# airball_sensor_board_v3.net
KiCad netlist of a schematic drawn in EAGLE
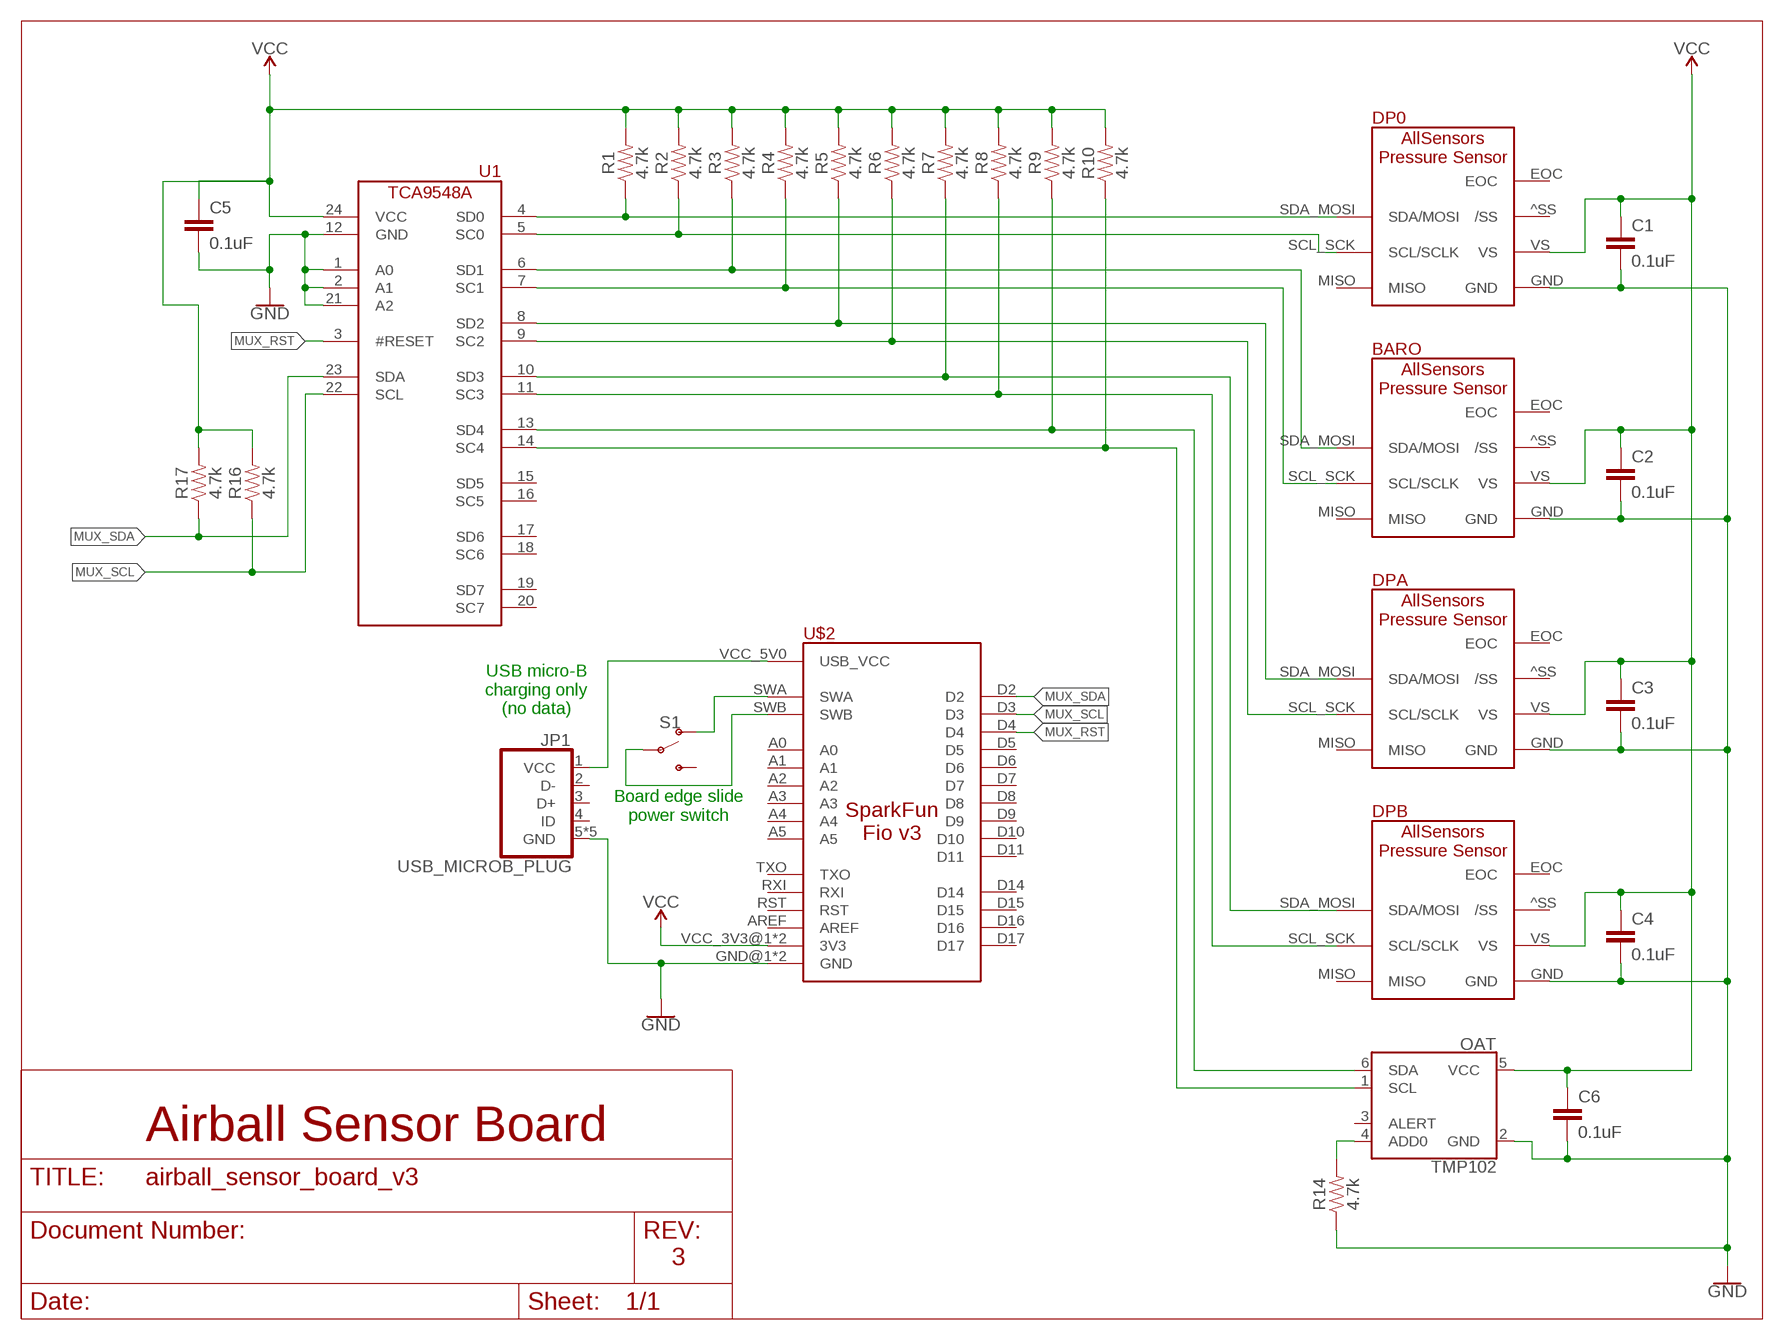
[diagram p0: schematic, sheet 1]

(export (version "E")
  (design (tool "Eeschema 10.0.6"))
  (components
    (comp (ref "BARO")
      (value "ALL_SENSORS_DLHR_E1ND")
      (footprint "eagle-import:ALL_SENSORS_E1BD_8PIN_THRU")
      (libsource (lib "eagle-import") (part "ALL_SENSORS_DLHR_E1ND"))
    )
    (comp (ref "C1")
      (value "0.1uF")
      (footprint "eagle-import:0603")
      (libsource (lib "eagle-import") (part "0.1UF-0603-25V-5%"))
    )
    (comp (ref "C2")
      (value "0.1uF")
      (footprint "eagle-import:0603")
      (libsource (lib "eagle-import") (part "0.1UF-0603-25V-5%"))
    )
    (comp (ref "C3")
      (value "0.1uF")
      (footprint "eagle-import:0603")
      (libsource (lib "eagle-import") (part "0.1UF-0603-25V-5%"))
    )
    (comp (ref "C4")
      (value "0.1uF")
      (footprint "eagle-import:0603")
      (libsource (lib "eagle-import") (part "0.1UF-0603-25V-5%"))
    )
    (comp (ref "C5")
      (value "0.1uF")
      (footprint "eagle-import:0603")
      (libsource (lib "eagle-import") (part "0.1UF-0603-25V-5%"))
    )
    (comp (ref "C6")
      (value "0.1uF")
      (footprint "eagle-import:0603")
      (libsource (lib "eagle-import") (part "0.1UF-0603-25V-5%"))
    )
    (comp (ref "DP0")
      (value "ALL_SENSORS_DLHR_E1ND")
      (footprint "eagle-import:ALL_SENSORS_E1BD_8PIN_THRU")
      (libsource (lib "eagle-import") (part "ALL_SENSORS_DLHR_E1ND"))
    )
    (comp (ref "DPA")
      (value "ALL_SENSORS_DLHR_E1ND")
      (footprint "eagle-import:ALL_SENSORS_E1BD_8PIN_THRU")
      (libsource (lib "eagle-import") (part "ALL_SENSORS_DLHR_E1ND"))
    )
    (comp (ref "DPB")
      (value "ALL_SENSORS_DLHR_E1ND")
      (footprint "eagle-import:ALL_SENSORS_E1BD_8PIN_THRU")
      (libsource (lib "eagle-import") (part "ALL_SENSORS_DLHR_E1ND"))
    )
    (comp (ref "JP1")
      (value "USB_MICROB_PLUG")
      (footprint "eagle-import:USB_MICRO_B_TYCO")
      (libsource (lib "eagle-import") (part "USB_MICROB_PLUG"))
    )
    (comp (ref "OAT")
      (value "TMP102")
      (footprint "eagle-import:SOT563")
      (libsource (lib "eagle-import") (part "TMP102"))
    )
    (comp (ref "R1")
      (value "4.7k")
      (footprint "eagle-import:0603")
      (libsource (lib "eagle-import") (part "4.7KOHM-0603-1/10W-1%"))
    )
    (comp (ref "R2")
      (value "4.7k")
      (footprint "eagle-import:0603")
      (libsource (lib "eagle-import") (part "4.7KOHM-0603-1/10W-1%"))
    )
    (comp (ref "R3")
      (value "4.7k")
      (footprint "eagle-import:0603")
      (libsource (lib "eagle-import") (part "4.7KOHM-0603-1/10W-1%"))
    )
    (comp (ref "R4")
      (value "4.7k")
      (footprint "eagle-import:0603")
      (libsource (lib "eagle-import") (part "4.7KOHM-0603-1/10W-1%"))
    )
    (comp (ref "R5")
      (value "4.7k")
      (footprint "eagle-import:0603")
      (libsource (lib "eagle-import") (part "4.7KOHM-0603-1/10W-1%"))
    )
    (comp (ref "R6")
      (value "4.7k")
      (footprint "eagle-import:0603")
      (libsource (lib "eagle-import") (part "4.7KOHM-0603-1/10W-1%"))
    )
    (comp (ref "R7")
      (value "4.7k")
      (footprint "eagle-import:0603")
      (libsource (lib "eagle-import") (part "4.7KOHM-0603-1/10W-1%"))
    )
    (comp (ref "R8")
      (value "4.7k")
      (footprint "eagle-import:0603")
      (libsource (lib "eagle-import") (part "4.7KOHM-0603-1/10W-1%"))
    )
    (comp (ref "R9")
      (value "4.7k")
      (footprint "eagle-import:0603")
      (libsource (lib "eagle-import") (part "4.7KOHM-0603-1/10W-1%"))
    )
    (comp (ref "R10")
      (value "4.7k")
      (footprint "eagle-import:0603")
      (libsource (lib "eagle-import") (part "4.7KOHM-0603-1/10W-1%"))
    )
    (comp (ref "R14")
      (value "4.7k")
      (footprint "eagle-import:0603")
      (libsource (lib "eagle-import") (part "4.7KOHM-0603-1/10W-1%"))
    )
    (comp (ref "R16")
      (value "4.7k")
      (footprint "eagle-import:0603")
      (libsource (lib "eagle-import") (part "4.7KOHM-0603-1/10W-1%"))
    )
    (comp (ref "R17")
      (value "4.7k")
      (footprint "eagle-import:0603")
      (libsource (lib "eagle-import") (part "4.7KOHM-0603-1/10W-1%"))
    )
    (comp (ref "S1")
      (value "SWITCH-SPDT-SMD-RIGHT-ANGLE")
      (footprint "eagle-import:SWITCH_SPST_SMD_A")
      (libsource (lib "eagle-import") (part "SWITCH-SPDT-SMD-RIGHT-ANGLE"))
    )
    (comp (ref "U$2")
      (value "SPARKFUN_FIO_V3")
      (footprint "eagle-import:SPARKFUN_FIO_V3")
      (libsource (lib "eagle-import") (part "SPARKFUN_FIO_V3"))
    )
    (comp (ref "U1")
      (value "TCA9548ATSSOP24")
      (footprint "eagle-import:TSSOP24")
      (libsource (lib "eagle-import") (part "TCA9548ATSSOP24"))
    )
  )
  (nets
    (net (code "1") (name "GND") (class "Default")
      (node (ref "BARO") (pin "GND") (pinfunction "GND_GND") (pintype "power_in"))
      (node (ref "C1") (pin "2") (pinfunction "2_2") (pintype "passive"))
      (node (ref "C2") (pin "2") (pinfunction "2_2") (pintype "passive"))
      (node (ref "C3") (pin "2") (pinfunction "2_2") (pintype "passive"))
      (node (ref "C4") (pin "2") (pinfunction "2_2") (pintype "passive"))
      (node (ref "C5") (pin "2") (pinfunction "2_2") (pintype "passive"))
      (node (ref "C6") (pin "2") (pinfunction "2_2") (pintype "passive"))
      (node (ref "DP0") (pin "GND") (pinfunction "GND_GND") (pintype "power_in"))
      (node (ref "DPA") (pin "GND") (pinfunction "GND_GND") (pintype "power_in"))
      (node (ref "DPB") (pin "GND") (pinfunction "GND_GND") (pintype "power_in"))
      (node (ref "JP1") (pin "5") (pinfunction "GND_5") (pintype "bidirectional"))
      (node (ref "JP1") (pin "SH@1") (pinfunction "GND_SH@1") (pintype "bidirectional"))
      (node (ref "JP1") (pin "SH@2") (pinfunction "GND_SH@2") (pintype "bidirectional"))
      (node (ref "JP1") (pin "SH@3") (pinfunction "GND_SH@3") (pintype "bidirectional"))
      (node (ref "JP1") (pin "SH@4") (pinfunction "GND_SH@4") (pintype "bidirectional"))
      (node (ref "OAT") (pin "2") (pinfunction "GND_2") (pintype "bidirectional"))
      (node (ref "R14") (pin "1") (pinfunction "1_1") (pintype "passive"))
      (node (ref "U$2") (pin "GND@1") (pinfunction "GND_GND@1") (pintype "power_in"))
      (node (ref "U$2") (pin "GND@2") (pinfunction "GND_GND@2") (pintype "power_in"))
      (node (ref "U1") (pin "1") (pinfunction "A0_1") (pintype "bidirectional"))
      (node (ref "U1") (pin "12") (pinfunction "GND_12") (pintype "bidirectional"))
      (node (ref "U1") (pin "2") (pinfunction "A1_2") (pintype "bidirectional"))
      (node (ref "U1") (pin "21") (pinfunction "A2_21") (pintype "bidirectional"))
    )
    (net (code "2") (name "MUX_RST") (class "Default")
      (node (ref "U$2") (pin "D4") (pinfunction "D4_D4") (pintype "bidirectional"))
      (node (ref "U1") (pin "3") (pinfunction "#RESET_3") (pintype "bidirectional"))
    )
    (net (code "3") (name "MUX_SCL") (class "Default")
      (node (ref "R16") (pin "1") (pinfunction "1_1") (pintype "passive"))
      (node (ref "U$2") (pin "D3") (pinfunction "D3_D3") (pintype "bidirectional"))
      (node (ref "U1") (pin "22") (pinfunction "SCL_22") (pintype "bidirectional"))
    )
    (net (code "4") (name "MUX_SDA") (class "Default")
      (node (ref "R17") (pin "1") (pinfunction "1_1") (pintype "passive"))
      (node (ref "U$2") (pin "D2") (pinfunction "D2_D2") (pintype "bidirectional"))
      (node (ref "U1") (pin "23") (pinfunction "SDA_23") (pintype "bidirectional"))
    )
    (net (code "5") (name "Net-(BARO-SCL{slash}SCLK)") (class "Default")
      (node (ref "BARO") (pin "SCL_SCK") (pinfunction "SCL/SCLK_SCL_SCK") (pintype "bidirectional"))
      (node (ref "R4") (pin "1") (pinfunction "1_1") (pintype "passive"))
      (node (ref "U1") (pin "7") (pinfunction "SC1_7") (pintype "bidirectional"))
    )
    (net (code "6") (name "Net-(BARO-SDA{slash}MOSI)") (class "Default")
      (node (ref "BARO") (pin "SDA_MOSI") (pinfunction "SDA/MOSI_SDA_MOSI") (pintype "bidirectional"))
      (node (ref "R3") (pin "1") (pinfunction "1_1") (pintype "passive"))
      (node (ref "U1") (pin "6") (pinfunction "SD1_6") (pintype "bidirectional"))
    )
    (net (code "7") (name "Net-(DP0-SCL{slash}SCLK)") (class "Default")
      (node (ref "DP0") (pin "SCL_SCK") (pinfunction "SCL/SCLK_SCL_SCK") (pintype "bidirectional"))
      (node (ref "R2") (pin "1") (pinfunction "1_1") (pintype "passive"))
      (node (ref "U1") (pin "5") (pinfunction "SC0_5") (pintype "bidirectional"))
    )
    (net (code "8") (name "Net-(DP0-SDA{slash}MOSI)") (class "Default")
      (node (ref "DP0") (pin "SDA_MOSI") (pinfunction "SDA/MOSI_SDA_MOSI") (pintype "bidirectional"))
      (node (ref "R1") (pin "1") (pinfunction "1_1") (pintype "passive"))
      (node (ref "U1") (pin "4") (pinfunction "SD0_4") (pintype "bidirectional"))
    )
    (net (code "9") (name "Net-(DPA-SCL{slash}SCLK)") (class "Default")
      (node (ref "DPA") (pin "SCL_SCK") (pinfunction "SCL/SCLK_SCL_SCK") (pintype "bidirectional"))
      (node (ref "R6") (pin "1") (pinfunction "1_1") (pintype "passive"))
      (node (ref "U1") (pin "9") (pinfunction "SC2_9") (pintype "bidirectional"))
    )
    (net (code "10") (name "Net-(DPA-SDA{slash}MOSI)") (class "Default")
      (node (ref "DPA") (pin "SDA_MOSI") (pinfunction "SDA/MOSI_SDA_MOSI") (pintype "bidirectional"))
      (node (ref "R5") (pin "1") (pinfunction "1_1") (pintype "passive"))
      (node (ref "U1") (pin "8") (pinfunction "SD2_8") (pintype "bidirectional"))
    )
    (net (code "11") (name "Net-(DPB-SCL{slash}SCLK)") (class "Default")
      (node (ref "DPB") (pin "SCL_SCK") (pinfunction "SCL/SCLK_SCL_SCK") (pintype "bidirectional"))
      (node (ref "R8") (pin "1") (pinfunction "1_1") (pintype "passive"))
      (node (ref "U1") (pin "11") (pinfunction "SC3_11") (pintype "bidirectional"))
    )
    (net (code "12") (name "Net-(DPB-SDA{slash}MOSI)") (class "Default")
      (node (ref "DPB") (pin "SDA_MOSI") (pinfunction "SDA/MOSI_SDA_MOSI") (pintype "bidirectional"))
      (node (ref "R7") (pin "1") (pinfunction "1_1") (pintype "passive"))
      (node (ref "U1") (pin "10") (pinfunction "SD3_10") (pintype "bidirectional"))
    )
    (net (code "13") (name "Net-(JP1-VCC)") (class "Default")
      (node (ref "JP1") (pin "1") (pinfunction "VCC_1") (pintype "bidirectional"))
      (node (ref "U$2") (pin "VCC_5V0") (pinfunction "USB_VCC_VCC_5V0") (pintype "power_in"))
    )
    (net (code "14") (name "Net-(OAT-ADD0)") (class "Default")
      (node (ref "OAT") (pin "4") (pinfunction "ADD0_4") (pintype "bidirectional"))
      (node (ref "R14") (pin "2") (pinfunction "2_2") (pintype "passive"))
    )
    (net (code "15") (name "Net-(OAT-SCL)") (class "Default")
      (node (ref "OAT") (pin "1") (pinfunction "SCL_1") (pintype "bidirectional"))
      (node (ref "R10") (pin "1") (pinfunction "1_1") (pintype "passive"))
      (node (ref "U1") (pin "14") (pinfunction "SC4_14") (pintype "bidirectional"))
    )
    (net (code "16") (name "Net-(OAT-SDA)") (class "Default")
      (node (ref "OAT") (pin "6") (pinfunction "SDA_6") (pintype "bidirectional"))
      (node (ref "R9") (pin "1") (pinfunction "1_1") (pintype "passive"))
      (node (ref "U1") (pin "13") (pinfunction "SD4_13") (pintype "bidirectional"))
    )
    (net (code "17") (name "Net-(S1-O)") (class "Default")
      (node (ref "S1") (pin "1") (pinfunction "O_1") (pintype "passive"))
      (node (ref "U$2") (pin "SWA") (pinfunction "SWA_SWA") (pintype "bidirectional"))
    )
    (net (code "18") (name "Net-(S1-P)") (class "Default")
      (node (ref "S1") (pin "2") (pinfunction "P_2") (pintype "passive"))
      (node (ref "U$2") (pin "SWB") (pinfunction "SWB_SWB") (pintype "bidirectional"))
    )
    (net (code "19") (name "VCC") (class "Default")
      (node (ref "BARO") (pin "VS") (pinfunction "VS_VS") (pintype "power_in"))
      (node (ref "C1") (pin "1") (pinfunction "1_1") (pintype "passive"))
      (node (ref "C2") (pin "1") (pinfunction "1_1") (pintype "passive"))
      (node (ref "C3") (pin "1") (pinfunction "1_1") (pintype "passive"))
      (node (ref "C4") (pin "1") (pinfunction "1_1") (pintype "passive"))
      (node (ref "C5") (pin "1") (pinfunction "1_1") (pintype "passive"))
      (node (ref "C6") (pin "1") (pinfunction "1_1") (pintype "passive"))
      (node (ref "DP0") (pin "VS") (pinfunction "VS_VS") (pintype "power_in"))
      (node (ref "DPA") (pin "VS") (pinfunction "VS_VS") (pintype "power_in"))
      (node (ref "DPB") (pin "VS") (pinfunction "VS_VS") (pintype "power_in"))
      (node (ref "OAT") (pin "5") (pinfunction "VCC_5") (pintype "bidirectional"))
      (node (ref "R1") (pin "2") (pinfunction "2_2") (pintype "passive"))
      (node (ref "R10") (pin "2") (pinfunction "2_2") (pintype "passive"))
      (node (ref "R16") (pin "2") (pinfunction "2_2") (pintype "passive"))
      (node (ref "R17") (pin "2") (pinfunction "2_2") (pintype "passive"))
      (node (ref "R2") (pin "2") (pinfunction "2_2") (pintype "passive"))
      (node (ref "R3") (pin "2") (pinfunction "2_2") (pintype "passive"))
      (node (ref "R4") (pin "2") (pinfunction "2_2") (pintype "passive"))
      (node (ref "R5") (pin "2") (pinfunction "2_2") (pintype "passive"))
      (node (ref "R6") (pin "2") (pinfunction "2_2") (pintype "passive"))
      (node (ref "R7") (pin "2") (pinfunction "2_2") (pintype "passive"))
      (node (ref "R8") (pin "2") (pinfunction "2_2") (pintype "passive"))
      (node (ref "R9") (pin "2") (pinfunction "2_2") (pintype "passive"))
      (node (ref "U$2") (pin "VCC_3V3@1") (pinfunction "3V3_VCC_3V3@1") (pintype "power_in"))
      (node (ref "U$2") (pin "VCC_3V3@2") (pinfunction "3V3_VCC_3V3@2") (pintype "power_in"))
      (node (ref "U1") (pin "24") (pinfunction "VCC_24") (pintype "bidirectional"))
    )
    (net (code "20") (name "unconnected-(BARO-PadEOC)") (class "Default")
      (node (ref "BARO") (pin "EOC") (pinfunction "EOC_EOC") (pintype "bidirectional"))
    )
    (net (code "21") (name "unconnected-(BARO-PadMISO)") (class "Default")
      (node (ref "BARO") (pin "MISO") (pinfunction "MISO_MISO") (pintype "input"))
    )
    (net (code "22") (name "unconnected-(BARO-{slash}SS-Pad^SS)") (class "Default")
      (node (ref "BARO") (pin "^SS") (pinfunction "/SS_^SS") (pintype "input"))
    )
    (net (code "23") (name "unconnected-(DP0-PadEOC)") (class "Default")
      (node (ref "DP0") (pin "EOC") (pinfunction "EOC_EOC") (pintype "bidirectional"))
    )
    (net (code "24") (name "unconnected-(DP0-PadMISO)") (class "Default")
      (node (ref "DP0") (pin "MISO") (pinfunction "MISO_MISO") (pintype "input"))
    )
    (net (code "25") (name "unconnected-(DP0-{slash}SS-Pad^SS)") (class "Default")
      (node (ref "DP0") (pin "^SS") (pinfunction "/SS_^SS") (pintype "input"))
    )
    (net (code "26") (name "unconnected-(DPA-PadEOC)") (class "Default")
      (node (ref "DPA") (pin "EOC") (pinfunction "EOC_EOC") (pintype "bidirectional"))
    )
    (net (code "27") (name "unconnected-(DPA-PadMISO)") (class "Default")
      (node (ref "DPA") (pin "MISO") (pinfunction "MISO_MISO") (pintype "input"))
    )
    (net (code "28") (name "unconnected-(DPA-{slash}SS-Pad^SS)") (class "Default")
      (node (ref "DPA") (pin "^SS") (pinfunction "/SS_^SS") (pintype "input"))
    )
    (net (code "29") (name "unconnected-(DPB-PadEOC)") (class "Default")
      (node (ref "DPB") (pin "EOC") (pinfunction "EOC_EOC") (pintype "bidirectional"))
    )
    (net (code "30") (name "unconnected-(DPB-PadMISO)") (class "Default")
      (node (ref "DPB") (pin "MISO") (pinfunction "MISO_MISO") (pintype "input"))
    )
    (net (code "31") (name "unconnected-(DPB-{slash}SS-Pad^SS)") (class "Default")
      (node (ref "DPB") (pin "^SS") (pinfunction "/SS_^SS") (pintype "input"))
    )
    (net (code "32") (name "unconnected-(JP1-D+-Pad3)") (class "Default")
      (node (ref "JP1") (pin "3") (pinfunction "D+_3") (pintype "bidirectional"))
    )
    (net (code "33") (name "unconnected-(JP1-D--Pad2)") (class "Default")
      (node (ref "JP1") (pin "2") (pinfunction "D-_2") (pintype "bidirectional"))
    )
    (net (code "34") (name "unconnected-(JP1-ID-Pad4)") (class "Default")
      (node (ref "JP1") (pin "4") (pinfunction "ID_4") (pintype "bidirectional"))
    )
    (net (code "35") (name "unconnected-(OAT-ALERT-Pad3)") (class "Default")
      (node (ref "OAT") (pin "3") (pinfunction "ALERT_3") (pintype "bidirectional"))
    )
    (net (code "36") (name "unconnected-(S1-S-Pad3)") (class "Default")
      (node (ref "S1") (pin "3") (pinfunction "S_3") (pintype "passive"))
    )
    (net (code "37") (name "unconnected-(U$2-PadA0)") (class "Default")
      (node (ref "U$2") (pin "A0") (pinfunction "A0_A0") (pintype "bidirectional"))
    )
    (net (code "38") (name "unconnected-(U$2-PadA1)") (class "Default")
      (node (ref "U$2") (pin "A1") (pinfunction "A1_A1") (pintype "bidirectional"))
    )
    (net (code "39") (name "unconnected-(U$2-PadA2)") (class "Default")
      (node (ref "U$2") (pin "A2") (pinfunction "A2_A2") (pintype "bidirectional"))
    )
    (net (code "40") (name "unconnected-(U$2-PadA3)") (class "Default")
      (node (ref "U$2") (pin "A3") (pinfunction "A3_A3") (pintype "bidirectional"))
    )
    (net (code "41") (name "unconnected-(U$2-PadA4)") (class "Default")
      (node (ref "U$2") (pin "A4") (pinfunction "A4_A4") (pintype "bidirectional"))
    )
    (net (code "42") (name "unconnected-(U$2-PadA5)") (class "Default")
      (node (ref "U$2") (pin "A5") (pinfunction "A5_A5") (pintype "bidirectional"))
    )
    (net (code "43") (name "unconnected-(U$2-PadAREF)") (class "Default")
      (node (ref "U$2") (pin "AREF") (pinfunction "AREF_AREF") (pintype "bidirectional"))
    )
    (net (code "44") (name "unconnected-(U$2-PadD5)") (class "Default")
      (node (ref "U$2") (pin "D5") (pinfunction "D5_D5") (pintype "bidirectional"))
    )
    (net (code "45") (name "unconnected-(U$2-PadD6)") (class "Default")
      (node (ref "U$2") (pin "D6") (pinfunction "D6_D6") (pintype "bidirectional"))
    )
    (net (code "46") (name "unconnected-(U$2-PadD7)") (class "Default")
      (node (ref "U$2") (pin "D7") (pinfunction "D7_D7") (pintype "bidirectional"))
    )
    (net (code "47") (name "unconnected-(U$2-PadD8)") (class "Default")
      (node (ref "U$2") (pin "D8") (pinfunction "D8_D8") (pintype "bidirectional"))
    )
    (net (code "48") (name "unconnected-(U$2-PadD9)") (class "Default")
      (node (ref "U$2") (pin "D9") (pinfunction "D9_D9") (pintype "bidirectional"))
    )
    (net (code "49") (name "unconnected-(U$2-PadD10)") (class "Default")
      (node (ref "U$2") (pin "D10") (pinfunction "D10_D10") (pintype "bidirectional"))
    )
    (net (code "50") (name "unconnected-(U$2-PadD11)") (class "Default")
      (node (ref "U$2") (pin "D11") (pinfunction "D11_D11") (pintype "bidirectional"))
    )
    (net (code "51") (name "unconnected-(U$2-PadD14)") (class "Default")
      (node (ref "U$2") (pin "D14") (pinfunction "D14_D14") (pintype "bidirectional"))
    )
    (net (code "52") (name "unconnected-(U$2-PadD15)") (class "Default")
      (node (ref "U$2") (pin "D15") (pinfunction "D15_D15") (pintype "bidirectional"))
    )
    (net (code "53") (name "unconnected-(U$2-PadD16)") (class "Default")
      (node (ref "U$2") (pin "D16") (pinfunction "D16_D16") (pintype "bidirectional"))
    )
    (net (code "54") (name "unconnected-(U$2-PadD17)") (class "Default")
      (node (ref "U$2") (pin "D17") (pinfunction "D17_D17") (pintype "bidirectional"))
    )
    (net (code "55") (name "unconnected-(U$2-PadRST)") (class "Default")
      (node (ref "U$2") (pin "RST") (pinfunction "RST_RST") (pintype "bidirectional"))
    )
    (net (code "56") (name "unconnected-(U$2-PadRXI)") (class "Default")
      (node (ref "U$2") (pin "RXI") (pinfunction "RXI_RXI") (pintype "input"))
    )
    (net (code "57") (name "unconnected-(U$2-PadTXO)") (class "Default")
      (node (ref "U$2") (pin "TXO") (pinfunction "TXO_TXO") (pintype "output"))
    )
    (net (code "58") (name "unconnected-(U1-SC5-Pad16)") (class "Default")
      (node (ref "U1") (pin "16") (pinfunction "SC5_16") (pintype "bidirectional"))
    )
    (net (code "59") (name "unconnected-(U1-SC6-Pad18)") (class "Default")
      (node (ref "U1") (pin "18") (pinfunction "SC6_18") (pintype "bidirectional"))
    )
    (net (code "60") (name "unconnected-(U1-SC7-Pad20)") (class "Default")
      (node (ref "U1") (pin "20") (pinfunction "SC7_20") (pintype "bidirectional"))
    )
    (net (code "61") (name "unconnected-(U1-SD5-Pad15)") (class "Default")
      (node (ref "U1") (pin "15") (pinfunction "SD5_15") (pintype "bidirectional"))
    )
    (net (code "62") (name "unconnected-(U1-SD6-Pad17)") (class "Default")
      (node (ref "U1") (pin "17") (pinfunction "SD6_17") (pintype "bidirectional"))
    )
    (net (code "63") (name "unconnected-(U1-SD7-Pad19)") (class "Default")
      (node (ref "U1") (pin "19") (pinfunction "SD7_19") (pintype "bidirectional"))
    )
  )
)
